# Sensor-distance-long.net
KiCad netlist of a schematic drawn in EAGLE
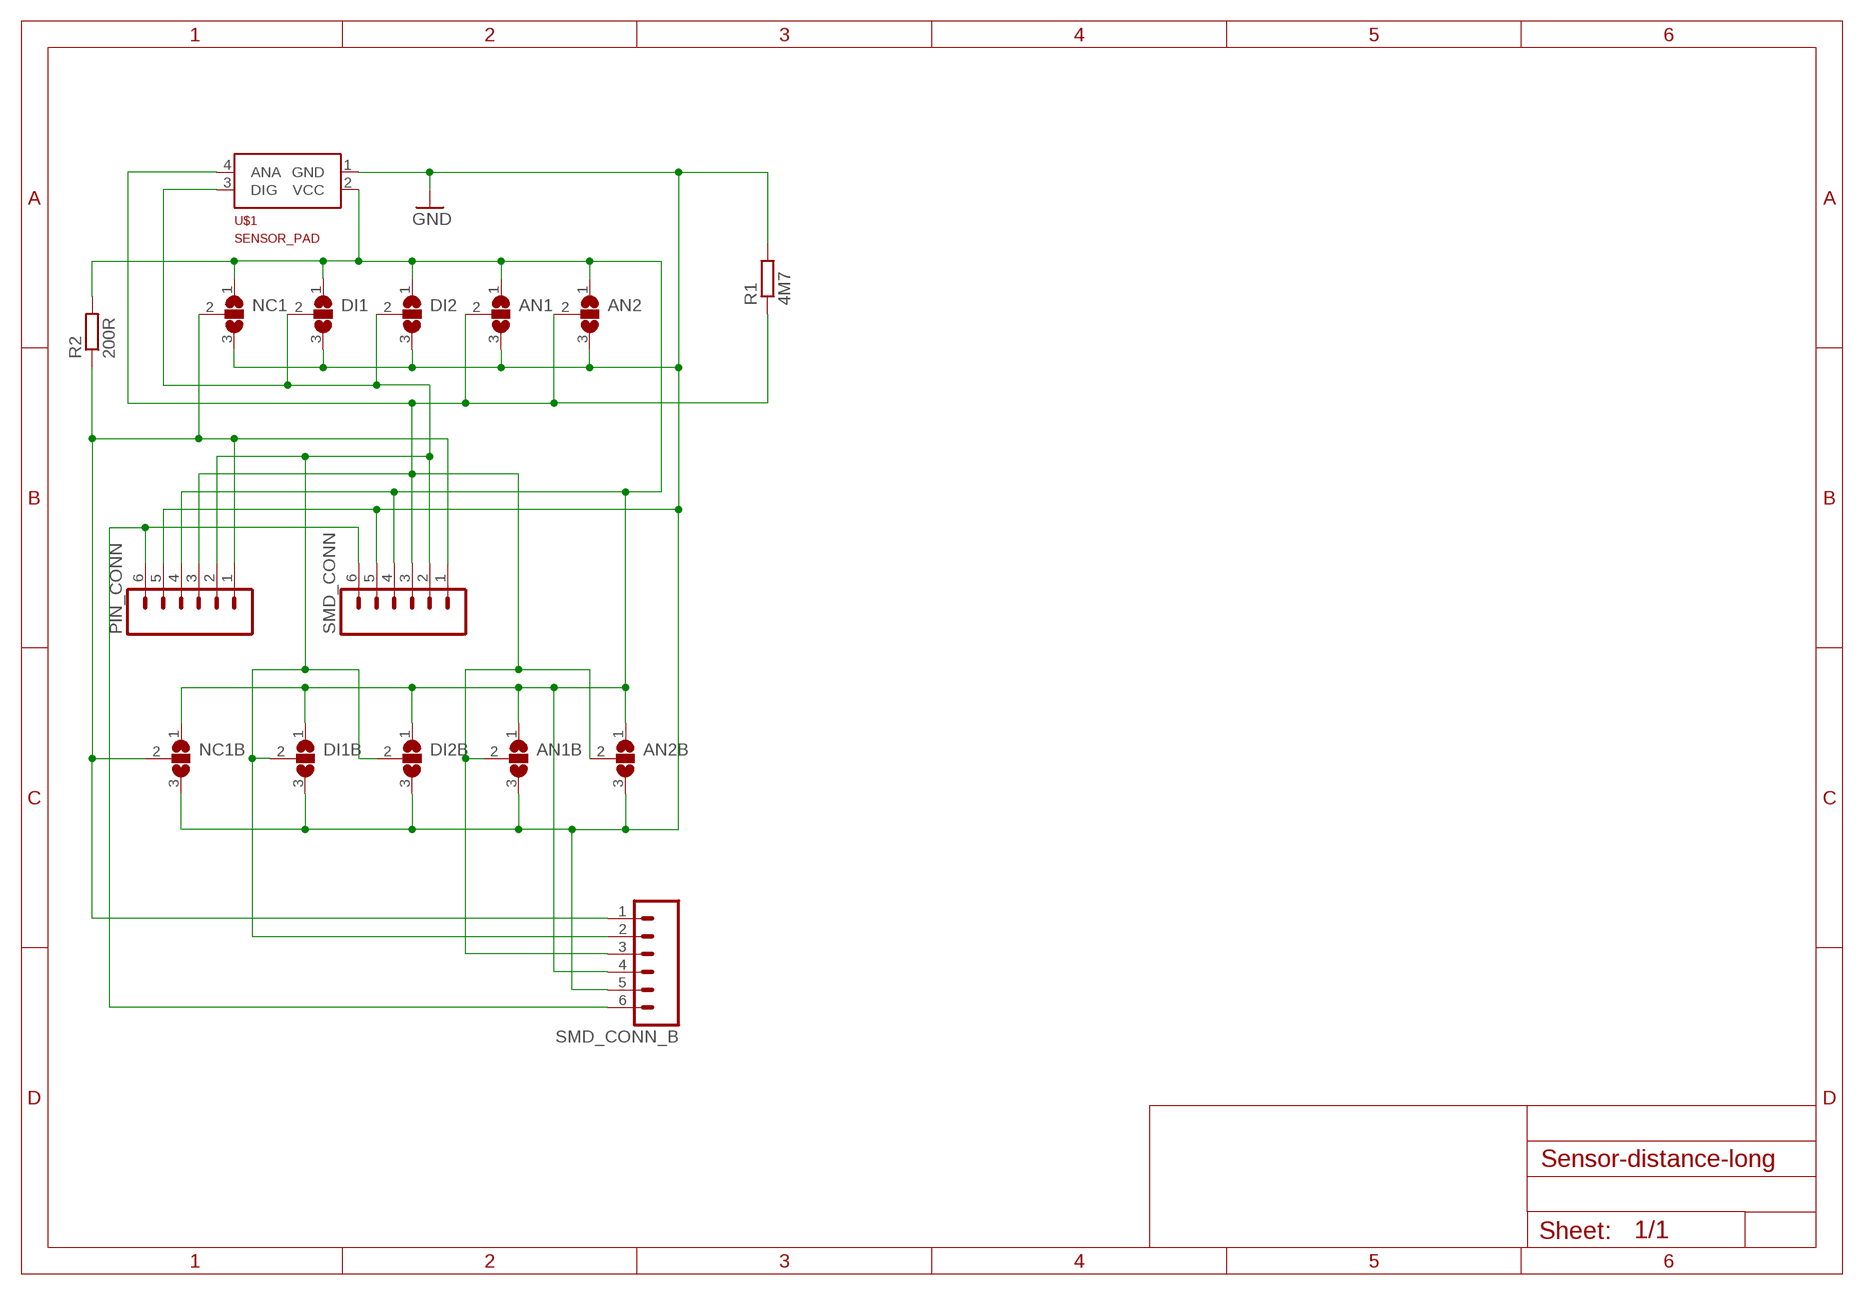
[diagram p0: schematic, sheet 1]

(export (version "E")
  (design (tool "Eeschema 10.0.6"))
  (components
    (comp (ref "AN1")
      (value "SJ2W")
      (footprint "eagle-import:SJ_2")
      (libsource (lib "eagle-import") (part "SJ2W"))
    )
    (comp (ref "AN1B")
      (value "SJ2W")
      (footprint "eagle-import:SJ_2")
      (libsource (lib "eagle-import") (part "SJ2W"))
    )
    (comp (ref "AN2")
      (value "SJ2W")
      (footprint "eagle-import:SJ_2")
      (libsource (lib "eagle-import") (part "SJ2W"))
    )
    (comp (ref "AN2B")
      (value "SJ2W")
      (footprint "eagle-import:SJ_2")
      (libsource (lib "eagle-import") (part "SJ2W"))
    )
    (comp (ref "DI1")
      (value "SJ2W")
      (footprint "eagle-import:SJ_2")
      (libsource (lib "eagle-import") (part "SJ2W"))
    )
    (comp (ref "DI1B")
      (value "SJ2W")
      (footprint "eagle-import:SJ_2")
      (libsource (lib "eagle-import") (part "SJ2W"))
    )
    (comp (ref "DI2")
      (value "SJ2W")
      (footprint "eagle-import:SJ_2")
      (libsource (lib "eagle-import") (part "SJ2W"))
    )
    (comp (ref "DI2B")
      (value "SJ2W")
      (footprint "eagle-import:SJ_2")
      (libsource (lib "eagle-import") (part "SJ2W"))
    )
    (comp (ref "NC1")
      (value "SJ2W")
      (footprint "eagle-import:SJ_2")
      (libsource (lib "eagle-import") (part "SJ2W"))
    )
    (comp (ref "NC1B")
      (value "SJ2W")
      (footprint "eagle-import:SJ_2")
      (libsource (lib "eagle-import") (part "SJ2W"))
    )
    (comp (ref "PIN_CONN")
      (value "M06SILK_FEMALE_PTH")
      (footprint "eagle-import:1X06")
      (libsource (lib "eagle-import") (part "M06SILK_FEMALE_PTH"))
    )
    (comp (ref "R1")
      (value "4M7")
      (footprint "eagle-import:R0805_SMALL")
      (fields (field (name "MF") "WELWYN") (field (name "MPN") "ASC0805-4M7FT5"))
      (libsource (lib "eagle-import") (part "R0805_SMALL"))
    )
    (comp (ref "R2")
      (value "200R")
      (footprint "eagle-import:R0805_SMALL")
      (fields (field (name "MF") "MULTICOMP") (field (name "MPN") "MCMR08X2000FTL"))
      (libsource (lib "eagle-import") (part "R0805_SMALL"))
    )
    (comp (ref "SMD_CONN")
      (value "M06SMD-STRAIGHT-COMBO-FEMALE")
      (footprint "eagle-import:1X06_SMD_STRAIGHT_COMBO")
      (libsource (lib "eagle-import") (part "M06SMD-STRAIGHT-COMBO-FEMALE"))
    )
    (comp (ref "SMD_CONN_B")
      (value "M06SMD-STRAIGHT-COMBO-FEMALE")
      (footprint "eagle-import:1X06_SMD_STRAIGHT_COMBO")
      (libsource (lib "eagle-import") (part "M06SMD-STRAIGHT-COMBO-FEMALE"))
    )
    (comp (ref "U$1")
      (value "SENSOR_PAD")
      (footprint "eagle-import:SENSOR_PAD")
      (libsource (lib "eagle-import") (part "SENSOR_PAD"))
    )
  )
  (nets
    (net (code "1") (name "GND") (class "Default")
      (node (ref "AN1") (pin "3") (pinfunction "3_3") (pintype "passive"))
      (node (ref "AN1B") (pin "3") (pinfunction "3_3") (pintype "passive"))
      (node (ref "AN2") (pin "3") (pinfunction "3_3") (pintype "passive"))
      (node (ref "AN2B") (pin "3") (pinfunction "3_3") (pintype "passive"))
      (node (ref "DI1") (pin "3") (pinfunction "3_3") (pintype "passive"))
      (node (ref "DI1B") (pin "3") (pinfunction "3_3") (pintype "passive"))
      (node (ref "DI2") (pin "3") (pinfunction "3_3") (pintype "passive"))
      (node (ref "DI2B") (pin "3") (pinfunction "3_3") (pintype "passive"))
      (node (ref "NC1") (pin "3") (pinfunction "3_3") (pintype "passive"))
      (node (ref "NC1B") (pin "3") (pinfunction "3_3") (pintype "passive"))
      (node (ref "PIN_CONN") (pin "5") (pinfunction "5_5") (pintype "passive"))
      (node (ref "R1") (pin "2") (pinfunction "2_2") (pintype "passive"))
      (node (ref "SMD_CONN") (pin "5") (pinfunction "5_5") (pintype "passive"))
      (node (ref "SMD_CONN_B") (pin "5") (pinfunction "5_5") (pintype "passive"))
      (node (ref "U$1") (pin "1") (pinfunction "GND_1") (pintype "bidirectional"))
    )
    (net (code "2") (name "Net-(NC1-Pad2)") (class "Default")
      (node (ref "NC1") (pin "2") (pinfunction "2_2") (pintype "passive"))
      (node (ref "NC1B") (pin "2") (pinfunction "2_2") (pintype "passive"))
      (node (ref "PIN_CONN") (pin "1") (pinfunction "1_1") (pintype "passive"))
      (node (ref "R2") (pin "1") (pinfunction "1_1") (pintype "passive"))
      (node (ref "SMD_CONN") (pin "1") (pinfunction "1_1") (pintype "passive"))
      (node (ref "SMD_CONN_B") (pin "1") (pinfunction "1_1") (pintype "passive"))
    )
    (net (code "3") (name "Net-(PIN_CONN-Pad6)") (class "Default")
      (node (ref "PIN_CONN") (pin "6") (pinfunction "6_6") (pintype "passive"))
      (node (ref "SMD_CONN") (pin "6") (pinfunction "6_6") (pintype "passive"))
      (node (ref "SMD_CONN_B") (pin "6") (pinfunction "6_6") (pintype "passive"))
    )
    (net (code "4") (name "Net-(U$1-ANA)") (class "Default")
      (node (ref "AN1") (pin "2") (pinfunction "2_2") (pintype "passive"))
      (node (ref "AN1B") (pin "2") (pinfunction "2_2") (pintype "passive"))
      (node (ref "AN2") (pin "2") (pinfunction "2_2") (pintype "passive"))
      (node (ref "AN2B") (pin "2") (pinfunction "2_2") (pintype "passive"))
      (node (ref "PIN_CONN") (pin "3") (pinfunction "3_3") (pintype "passive"))
      (node (ref "R1") (pin "1") (pinfunction "1_1") (pintype "passive"))
      (node (ref "SMD_CONN") (pin "3") (pinfunction "3_3") (pintype "passive"))
      (node (ref "SMD_CONN_B") (pin "3") (pinfunction "3_3") (pintype "passive"))
      (node (ref "U$1") (pin "4") (pinfunction "ANA_4") (pintype "bidirectional"))
    )
    (net (code "5") (name "Net-(U$1-DIG)") (class "Default")
      (node (ref "DI1") (pin "2") (pinfunction "2_2") (pintype "passive"))
      (node (ref "DI1B") (pin "2") (pinfunction "2_2") (pintype "passive"))
      (node (ref "DI2") (pin "2") (pinfunction "2_2") (pintype "passive"))
      (node (ref "DI2B") (pin "2") (pinfunction "2_2") (pintype "passive"))
      (node (ref "PIN_CONN") (pin "2") (pinfunction "2_2") (pintype "passive"))
      (node (ref "SMD_CONN") (pin "2") (pinfunction "2_2") (pintype "passive"))
      (node (ref "SMD_CONN_B") (pin "2") (pinfunction "2_2") (pintype "passive"))
      (node (ref "U$1") (pin "3") (pinfunction "DIG_3") (pintype "bidirectional"))
    )
    (net (code "6") (name "Net-(U$1-VCC)") (class "Default")
      (node (ref "AN1") (pin "1") (pinfunction "1_1") (pintype "passive"))
      (node (ref "AN1B") (pin "1") (pinfunction "1_1") (pintype "passive"))
      (node (ref "AN2") (pin "1") (pinfunction "1_1") (pintype "passive"))
      (node (ref "AN2B") (pin "1") (pinfunction "1_1") (pintype "passive"))
      (node (ref "DI1") (pin "1") (pinfunction "1_1") (pintype "passive"))
      (node (ref "DI1B") (pin "1") (pinfunction "1_1") (pintype "passive"))
      (node (ref "DI2") (pin "1") (pinfunction "1_1") (pintype "passive"))
      (node (ref "DI2B") (pin "1") (pinfunction "1_1") (pintype "passive"))
      (node (ref "NC1") (pin "1") (pinfunction "1_1") (pintype "passive"))
      (node (ref "NC1B") (pin "1") (pinfunction "1_1") (pintype "passive"))
      (node (ref "PIN_CONN") (pin "4") (pinfunction "4_4") (pintype "passive"))
      (node (ref "R2") (pin "2") (pinfunction "2_2") (pintype "passive"))
      (node (ref "SMD_CONN") (pin "4") (pinfunction "4_4") (pintype "passive"))
      (node (ref "SMD_CONN_B") (pin "4") (pinfunction "4_4") (pintype "passive"))
      (node (ref "U$1") (pin "2") (pinfunction "VCC_2") (pintype "bidirectional"))
    )
  )
)
